# LCD.net
KiCad netlist of a schematic drawn in Altium Designer
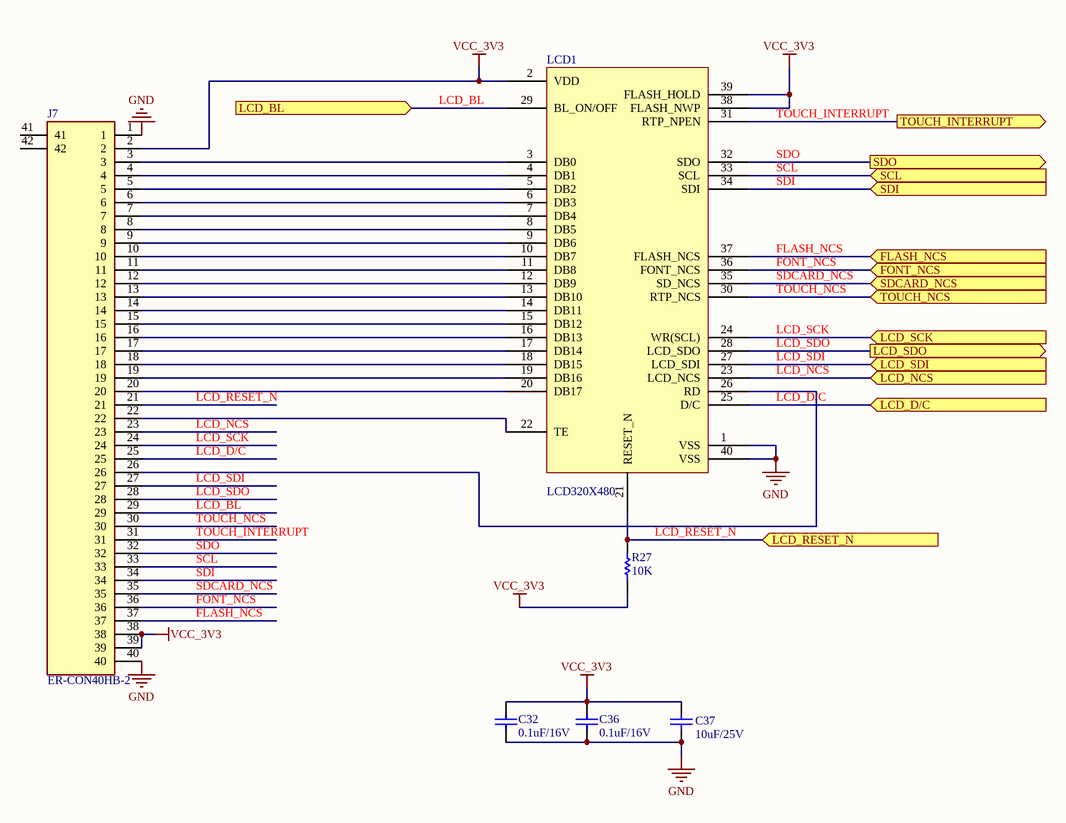
[diagram p0: LCD.SchDoc]

(export (version "E")
  (design (tool "Eeschema 10.0.6"))
  (components
    (comp (ref "C32")
      (value "0.1uF/16V")
      (footprint "0603C")
      (description "Multilayer Ceramic Capacitors MLCC - SMD/SMT 0603 16VDC 0.1uF 10% X7R AEC-Q2000")
      (fields (field (name "MFR") "Taiyo Yuden") (field (name "MFR PART NO") "EMK107B7104KAHT"))
      (libsource (lib "Miscellaneous Devices") (part "Cap"))
    )
    (comp (ref "C36")
      (value "0.1uF/16V")
      (footprint "0603C")
      (description "Multilayer Ceramic Capacitors MLCC - SMD/SMT 0603 16VDC 0.1uF 10% X7R AEC-Q2000")
      (fields (field (name "MFR") "Taiyo Yuden") (field (name "MFR PART NO") "EMK107B7104KAHT"))
      (libsource (lib "Miscellaneous Devices") (part "Cap"))
    )
    (comp (ref "C37")
      (value "10uF/25V")
      (footprint "0805C")
      (description "Multilayer Ceramic Capacitors MLCC - SMD/SMT 0805 25VDC 10uF 20% X5R")
      (fields (field (name "MFR") "Taiyo Yuden") (field (name "MFR PART NO") "TMK212BBJ106MG-T"))
      (libsource (lib "Miscellaneous Devices") (part "Cap"))
    )
    (comp (ref "J7")
      (value "ER-CON40HB-2")
      (footprint "ProjCLib:ERCON40HB2")
      (description "40 Pin 1.0mm Pitch Bottom Contact ZIF Connector,FPC Connector")
      (libsource (lib "*") (part "ER-CON40HB-2"))
    )
    (comp (ref "LCD1")
      (value "LCD320X480")
      (footprint "HDR2X20")
      (fields (field (name "MFR") "Buy LCD") (field (name "MFR PART NO") "ER-TFTM035-6"))
      (libsource (lib "Schlib1") (part "ER-TFTM035-6"))
    )
    (comp (ref "R27")
      (value "10K")
      (footprint "0603R")
      (description "Thick Film Resistors - SMD 0603 10Kohms 1% Anti-Sulfur AEC-Q200")
      (fields (field (name "MFR") "ROHM Semiconductor") (field (name "MFR PART NO") "SFR03EZPF1002"))
      (libsource (lib "Miscellaneous Devices") (part "Res1"))
    )
  )
  (nets
    (net (code "1") (name "/FLASH_NCS") (class "Default")
      (node (ref "J7") (pin "37") (pinfunction "37_37") (pintype "passive"))
      (node (ref "LCD1") (pin "37") (pinfunction "FLASH_NCS_37") (pintype "passive"))
    )
    (net (code "2") (name "/FONT_NCS") (class "Default")
      (node (ref "J7") (pin "36") (pinfunction "36_36") (pintype "passive"))
      (node (ref "LCD1") (pin "36") (pinfunction "FONT_NCS_36") (pintype "passive"))
    )
    (net (code "3") (name "/LCD_BL") (class "Default")
      (node (ref "J7") (pin "29") (pinfunction "29_29") (pintype "passive"))
      (node (ref "LCD1") (pin "29") (pinfunction "BL_ON/OFF_29") (pintype "passive"))
    )
    (net (code "4") (name "/LCD_D{slash}C") (class "Default")
      (node (ref "J7") (pin "25") (pinfunction "25_25") (pintype "passive"))
      (node (ref "LCD1") (pin "25") (pinfunction "D/C_25") (pintype "passive"))
    )
    (net (code "5") (name "/LCD_NCS") (class "Default")
      (node (ref "J7") (pin "23") (pinfunction "23_23") (pintype "passive"))
      (node (ref "LCD1") (pin "23") (pinfunction "LCD_NCS_23") (pintype "passive"))
    )
    (net (code "6") (name "/LCD_RESET_N") (class "Default")
      (node (ref "J7") (pin "21") (pinfunction "21_21") (pintype "passive"))
      (node (ref "LCD1") (pin "21") (pinfunction "RESET_N_21") (pintype "passive"))
      (node (ref "R27") (pin "1") (pinfunction "1_1") (pintype "passive"))
    )
    (net (code "7") (name "/LCD_SCK") (class "Default")
      (node (ref "J7") (pin "24") (pinfunction "24_24") (pintype "passive"))
      (node (ref "LCD1") (pin "24") (pinfunction "WR(SCL)_24") (pintype "passive"))
    )
    (net (code "8") (name "/LCD_SDI") (class "Default")
      (node (ref "J7") (pin "27") (pinfunction "27_27") (pintype "passive"))
      (node (ref "LCD1") (pin "27") (pinfunction "LCD_SDI_27") (pintype "passive"))
    )
    (net (code "9") (name "/LCD_SDO") (class "Default")
      (node (ref "J7") (pin "28") (pinfunction "28_28") (pintype "passive"))
      (node (ref "LCD1") (pin "28") (pinfunction "LCD_SDO_28") (pintype "passive"))
    )
    (net (code "10") (name "/SCL") (class "Default")
      (node (ref "J7") (pin "33") (pinfunction "33_33") (pintype "passive"))
      (node (ref "LCD1") (pin "33") (pinfunction "SCL_33") (pintype "passive"))
    )
    (net (code "11") (name "/SDCARD_NCS") (class "Default")
      (node (ref "J7") (pin "35") (pinfunction "35_35") (pintype "passive"))
      (node (ref "LCD1") (pin "35") (pinfunction "SD_NCS_35") (pintype "passive"))
    )
    (net (code "12") (name "/SDI") (class "Default")
      (node (ref "J7") (pin "34") (pinfunction "34_34") (pintype "passive"))
      (node (ref "LCD1") (pin "34") (pinfunction "SDI_34") (pintype "passive"))
    )
    (net (code "13") (name "/SDO") (class "Default")
      (node (ref "J7") (pin "32") (pinfunction "32_32") (pintype "passive"))
      (node (ref "LCD1") (pin "32") (pinfunction "SDO_32") (pintype "passive"))
    )
    (net (code "14") (name "/TOUCH_INTERRUPT") (class "Default")
      (node (ref "J7") (pin "31") (pinfunction "31_31") (pintype "passive"))
      (node (ref "LCD1") (pin "31") (pinfunction "RTP_NPEN_31") (pintype "passive"))
    )
    (net (code "15") (name "/TOUCH_NCS") (class "Default")
      (node (ref "J7") (pin "30") (pinfunction "30_30") (pintype "passive"))
      (node (ref "LCD1") (pin "30") (pinfunction "RTP_NCS_30") (pintype "passive"))
    )
    (net (code "16") (name "GND") (class "Default")
      (node (ref "C32") (pin "2") (pinfunction "2_2") (pintype "passive"))
      (node (ref "C36") (pin "2") (pinfunction "2_2") (pintype "passive"))
      (node (ref "C37") (pin "1") (pinfunction "1_1") (pintype "passive"))
      (node (ref "J7") (pin "1") (pinfunction "1_1") (pintype "passive"))
      (node (ref "J7") (pin "40") (pinfunction "40_40") (pintype "passive"))
      (node (ref "LCD1") (pin "1") (pinfunction "VSS_1") (pintype "passive"))
      (node (ref "LCD1") (pin "40") (pinfunction "VSS_40") (pintype "passive"))
    )
    (net (code "17") (name "Net-(LCD1-DB0)") (class "Default")
      (node (ref "J7") (pin "3") (pinfunction "3_3") (pintype "passive"))
      (node (ref "LCD1") (pin "3") (pinfunction "DB0_3") (pintype "passive"))
    )
    (net (code "18") (name "Net-(LCD1-DB1)") (class "Default")
      (node (ref "J7") (pin "4") (pinfunction "4_4") (pintype "passive"))
      (node (ref "LCD1") (pin "4") (pinfunction "DB1_4") (pintype "passive"))
    )
    (net (code "19") (name "Net-(LCD1-DB2)") (class "Default")
      (node (ref "J7") (pin "5") (pinfunction "5_5") (pintype "passive"))
      (node (ref "LCD1") (pin "5") (pinfunction "DB2_5") (pintype "passive"))
    )
    (net (code "20") (name "Net-(LCD1-DB3)") (class "Default")
      (node (ref "J7") (pin "6") (pinfunction "6_6") (pintype "passive"))
      (node (ref "LCD1") (pin "6") (pinfunction "DB3_6") (pintype "passive"))
    )
    (net (code "21") (name "Net-(LCD1-DB4)") (class "Default")
      (node (ref "J7") (pin "7") (pinfunction "7_7") (pintype "passive"))
      (node (ref "LCD1") (pin "7") (pinfunction "DB4_7") (pintype "passive"))
    )
    (net (code "22") (name "Net-(LCD1-DB5)") (class "Default")
      (node (ref "J7") (pin "8") (pinfunction "8_8") (pintype "passive"))
      (node (ref "LCD1") (pin "8") (pinfunction "DB5_8") (pintype "passive"))
    )
    (net (code "23") (name "Net-(LCD1-DB6)") (class "Default")
      (node (ref "J7") (pin "9") (pinfunction "9_9") (pintype "passive"))
      (node (ref "LCD1") (pin "9") (pinfunction "DB6_9") (pintype "passive"))
    )
    (net (code "24") (name "Net-(LCD1-DB7)") (class "Default")
      (node (ref "J7") (pin "10") (pinfunction "10_10") (pintype "passive"))
      (node (ref "LCD1") (pin "10") (pinfunction "DB7_10") (pintype "passive"))
    )
    (net (code "25") (name "Net-(LCD1-DB8)") (class "Default")
      (node (ref "J7") (pin "11") (pinfunction "11_11") (pintype "passive"))
      (node (ref "LCD1") (pin "11") (pinfunction "DB8_11") (pintype "passive"))
    )
    (net (code "26") (name "Net-(LCD1-DB9)") (class "Default")
      (node (ref "J7") (pin "12") (pinfunction "12_12") (pintype "passive"))
      (node (ref "LCD1") (pin "12") (pinfunction "DB9_12") (pintype "passive"))
    )
    (net (code "27") (name "Net-(LCD1-DB10)") (class "Default")
      (node (ref "J7") (pin "13") (pinfunction "13_13") (pintype "passive"))
      (node (ref "LCD1") (pin "13") (pinfunction "DB10_13") (pintype "passive"))
    )
    (net (code "28") (name "Net-(LCD1-DB11)") (class "Default")
      (node (ref "J7") (pin "14") (pinfunction "14_14") (pintype "passive"))
      (node (ref "LCD1") (pin "14") (pinfunction "DB11_14") (pintype "passive"))
    )
    (net (code "29") (name "Net-(LCD1-DB12)") (class "Default")
      (node (ref "J7") (pin "15") (pinfunction "15_15") (pintype "passive"))
      (node (ref "LCD1") (pin "15") (pinfunction "DB12_15") (pintype "passive"))
    )
    (net (code "30") (name "Net-(LCD1-DB13)") (class "Default")
      (node (ref "J7") (pin "16") (pinfunction "16_16") (pintype "passive"))
      (node (ref "LCD1") (pin "16") (pinfunction "DB13_16") (pintype "passive"))
    )
    (net (code "31") (name "Net-(LCD1-DB14)") (class "Default")
      (node (ref "J7") (pin "17") (pinfunction "17_17") (pintype "passive"))
      (node (ref "LCD1") (pin "17") (pinfunction "DB14_17") (pintype "passive"))
    )
    (net (code "32") (name "Net-(LCD1-DB15)") (class "Default")
      (node (ref "J7") (pin "18") (pinfunction "18_18") (pintype "passive"))
      (node (ref "LCD1") (pin "18") (pinfunction "DB15_18") (pintype "passive"))
    )
    (net (code "33") (name "Net-(LCD1-DB16)") (class "Default")
      (node (ref "J7") (pin "19") (pinfunction "19_19") (pintype "passive"))
      (node (ref "LCD1") (pin "19") (pinfunction "DB16_19") (pintype "passive"))
    )
    (net (code "34") (name "Net-(LCD1-DB17)") (class "Default")
      (node (ref "J7") (pin "20") (pinfunction "20_20") (pintype "passive"))
      (node (ref "LCD1") (pin "20") (pinfunction "DB17_20") (pintype "passive"))
    )
    (net (code "35") (name "Net-(LCD1-RD)") (class "Default")
      (node (ref "J7") (pin "26") (pinfunction "26_26") (pintype "passive"))
      (node (ref "LCD1") (pin "26") (pinfunction "RD_26") (pintype "passive"))
    )
    (net (code "36") (name "Net-(LCD1-TE)") (class "Default")
      (node (ref "J7") (pin "22") (pinfunction "22_22") (pintype "passive"))
      (node (ref "LCD1") (pin "22") (pinfunction "TE_22") (pintype "passive"))
    )
    (net (code "37") (name "VCC_3V3") (class "Default")
      (node (ref "C32") (pin "1") (pinfunction "1_1") (pintype "passive"))
      (node (ref "C36") (pin "1") (pinfunction "1_1") (pintype "passive"))
      (node (ref "C37") (pin "2") (pinfunction "2_2") (pintype "passive"))
      (node (ref "J7") (pin "2") (pinfunction "2_2") (pintype "passive"))
      (node (ref "J7") (pin "38") (pinfunction "38_38") (pintype "passive"))
      (node (ref "J7") (pin "39") (pinfunction "39_39") (pintype "passive"))
      (node (ref "LCD1") (pin "2") (pinfunction "VDD_2") (pintype "passive"))
      (node (ref "LCD1") (pin "38") (pinfunction "FLASH_NWP_38") (pintype "passive"))
      (node (ref "LCD1") (pin "39") (pinfunction "FLASH_HOLD_39") (pintype "passive"))
      (node (ref "R27") (pin "2") (pinfunction "2_2") (pintype "passive"))
    )
    (net (code "38") (name "unconnected-(J7-Pad41)") (class "Default")
      (node (ref "J7") (pin "41") (pinfunction "41_41") (pintype "passive"))
    )
    (net (code "39") (name "unconnected-(J7-Pad42)") (class "Default")
      (node (ref "J7") (pin "42") (pinfunction "42_42") (pintype "passive"))
    )
  )
)
